# Sensoren.net
KiCad netlist of a schematic drawn in Altium Designer
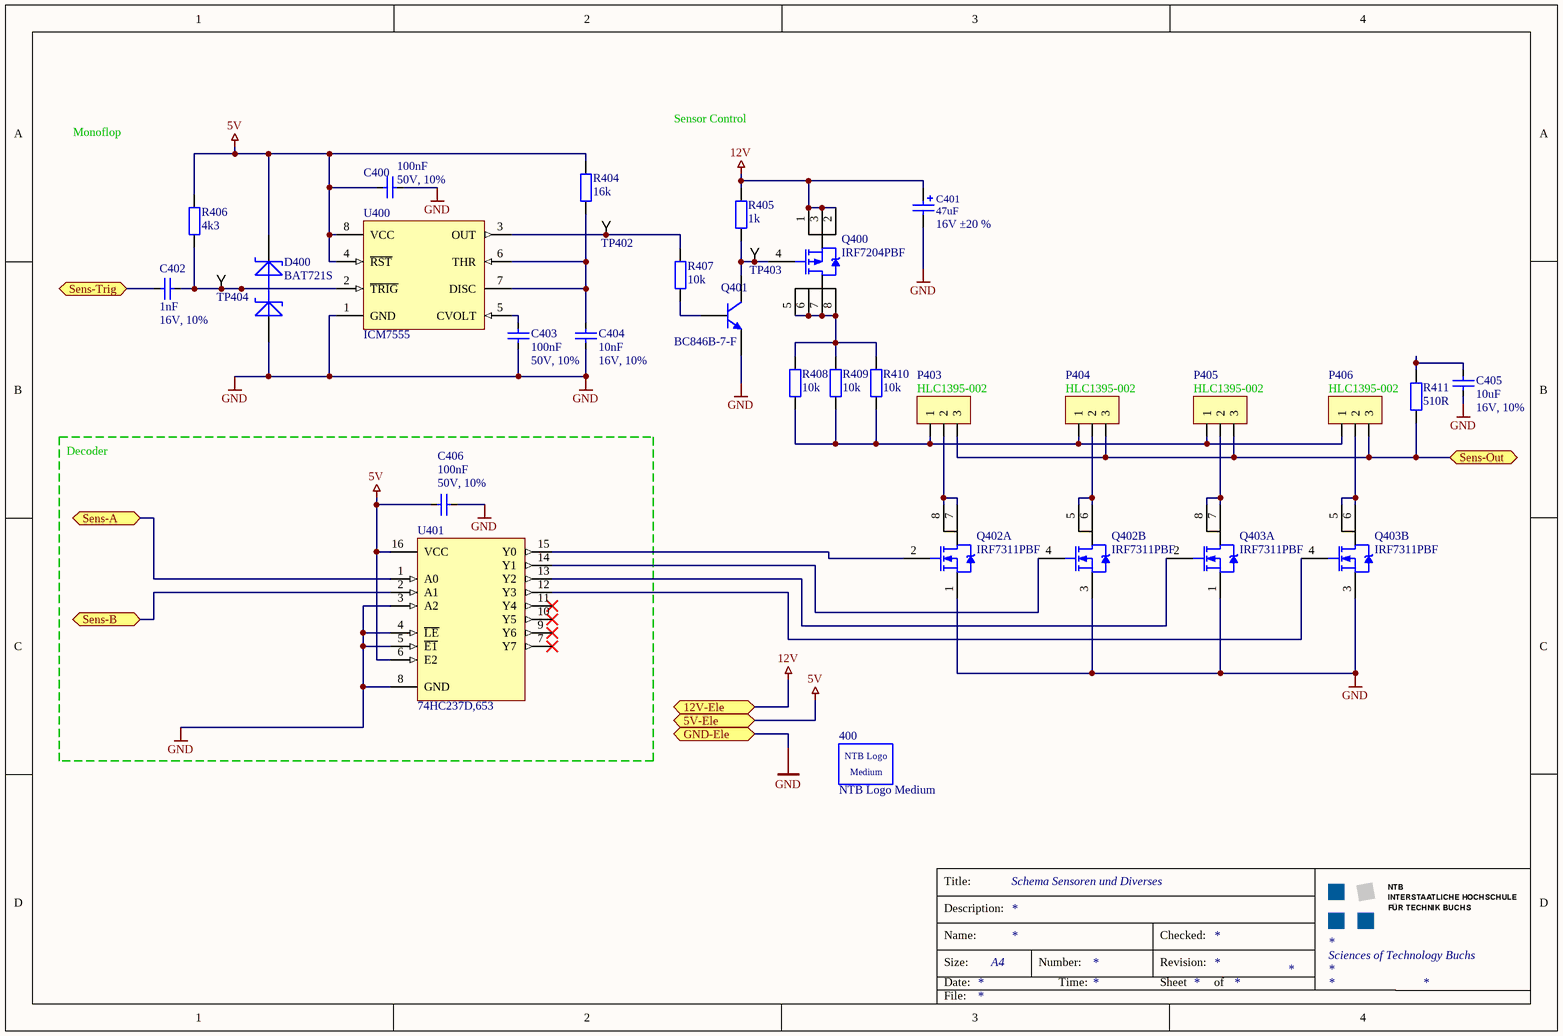
[diagram p0: Sensoren.SchDoc]

(export (version "E")
  (design (tool "Eeschema 10.0.6"))
  (components
    (comp (ref "400")
      (value "NTB Logo Medium")
      (footprint "NTB Logo Medium")
      (libsource (lib "IR-Sensor") (part "NTB Logo Medium"))
    )
    (comp (ref "C400")
      (value "100nF")
      (footprint "CAP-0805[2012]")
      (description "100n 50V X7R MLCC 0805 (1608 Metric)")
      (fields (field (name "TOLERANCE") "10%") (field (name "VALADDON") "50V, 10%"))
      (libsource (lib "IR-Sensor") (part "MLCC 0805 100n 50V"))
    )
    (comp (ref "C401")
      (value "47uF")
      (footprint "CDE_CAP AVE CODE D_H")
      (description "ELKO, 47uF, 16V, CDE_AVE476M16D16T-F_AVE CODE D")
      (fields
        (field (name "MANUFACTURER") "Cornell Dubilier")
        (field (name "VALUEADDON") "16V ±20 %")
        (field (name "Comment") "AVE476M16D16T-F")
        (field (name "PUBLISHER") "Stefan Ursella, M.Eng")
      )
      (libsource (lib "IR-Sensor") (part "ELKO 47uF 16V"))
    )
    (comp (ref "C402")
      (value "1nF")
      (footprint "CAP-0805[2012]")
      (description "MLCC - SMD/SMT 0805 1000pF 16V C0G 10%")
      (fields
        (field (name "MANUFACTURER") "Vishay")
        (field (name "VALUEADDON") "16V, 10%")
        (field (name "PUBLISHER") "SCLM")
      )
      (libsource (lib "IR-Sensor") (part "MLCC 0805 1n 16V"))
    )
    (comp (ref "C403")
      (value "100nF")
      (footprint "CAP-0805[2012]")
      (description "100n 50V X7R MLCC 0805 (1608 Metric)")
      (fields (field (name "TOLERANCE") "10%") (field (name "VALADDON") "50V, 10%"))
      (libsource (lib "IR-Sensor") (part "MLCC 0805 100n 50V"))
    )
    (comp (ref "C404")
      (value "10nF")
      (footprint "CAP-0805[2012]")
      (description "10n 16V X7R MLCC 0805")
      (fields
        (field (name "MANUFACTURER") "AVX")
        (field (name "VALUEADDON") "16V, 10%")
        (field (name "PUBLISHER") "SCLM")
      )
      (libsource (lib "IR-Sensor") (part "MLCC 0805 10n 16V"))
    )
    (comp (ref "C405")
      (value "10uF")
      (footprint "CAP-1206[3216]")
      (description "10u 16V X7R MLCC 1206 (3016 Metric)")
      (fields (field (name "TOLERANCE") "10%") (field (name "VALADDON") "16V, 10%"))
      (libsource (lib "IR-Sensor") (part "MLCC 1206 10u 16V"))
    )
    (comp (ref "C406")
      (value "100nF")
      (footprint "CAP-0805[2012]")
      (description "100n 50V X7R MLCC 0805 (1608 Metric)")
      (fields (field (name "TOLERANCE") "10%") (field (name "VALADDON") "50V, 10%"))
      (libsource (lib "IR-Sensor") (part "MLCC 0805 100n 50V"))
    )
    (comp (ref "D400")
      (value "BAT721S")
      (footprint "SOT-23")
      (description "NXP  BAT721S  SCHOTTKY-DIODE, 2FACH")
      (fields (field (name "MANUFACTURER") "NXP") (field (name "PUBLISHER") "SCNP"))
      (libsource (lib "IR-Sensor") (part "BAT721S-SOT23"))
    )
    (comp (ref "P403")
      (value "3 Pin Header Buchse")
      (footprint "3PIN HEADER SOCKET 2.54MM")
      (description "3 Pin Header 2.54mm Buchse")
      (libsource (lib "IR-Sensor") (part "3 Pin Header Buchse"))
    )
    (comp (ref "P404")
      (value "3 Pin Header Buchse")
      (footprint "3PIN HEADER SOCKET 2.54MM")
      (description "3 Pin Header 2.54mm Buchse")
      (libsource (lib "IR-Sensor") (part "3 Pin Header Buchse"))
    )
    (comp (ref "P405")
      (value "3 Pin Header Buchse")
      (footprint "3PIN HEADER SOCKET 2.54MM")
      (description "3 Pin Header 2.54mm Buchse")
      (libsource (lib "IR-Sensor") (part "3 Pin Header Buchse"))
    )
    (comp (ref "P406")
      (value "3 Pin Header Buchse")
      (footprint "3PIN HEADER SOCKET 2.54MM")
      (description "3 Pin Header 2.54mm Buchse")
      (libsource (lib "IR-Sensor") (part "3 Pin Header Buchse"))
    )
    (comp (ref "Q400")
      (value "IRF7204PBF")
      (footprint "SOIC-8")
      (description "High Power P-Kanal Mosfet")
      (fields
        (field (name "MANUFACTURER") "International Rectifiers")
        (field (name "PUBLISHER") "Altium Limited")
      )
      (libsource (lib "IR-Sensor") (part "IRF7204"))
    )
    (comp (ref "Q401")
      (value "BC846B-7-F")
      (footprint "SOT-23")
      (description "NPN General-purpose Transistor")
      (fields (field (name "MANUFACTURER") "DIODES INC") (field (name "PUBLISHER") "Altium Limited"))
      (libsource (lib "IR-Sensor") (part "BC846B-SOT23"))
    )
    (comp (ref "Q402")
      (value "IRF7311PBF")
      (footprint "SOIC-8")
      (description "Dual N-Kanal Mosfet")
      (fields
        (field (name "MANUFACTURER") "International Rectifier")
        (field (name "PUBLISHER") "Altium Limited")
      )
      (libsource (lib "IR-Sensor") (part "IRF7311"))
    )
    (comp (ref "Q403")
      (value "IRF7311PBF")
      (footprint "SOIC-8")
      (description "Dual N-Kanal Mosfet")
      (fields
        (field (name "MANUFACTURER") "International Rectifier")
        (field (name "PUBLISHER") "Altium Limited")
      )
      (libsource (lib "IR-Sensor") (part "IRF7311"))
    )
    (comp (ref "R404")
      (value "16k")
      (footprint "RES-0805[2012]")
      (description "0805 (2013 Metric) 1/10 W 10K 1 Thick Film Chip Resistor")
      (fields (field (name "POWER") "1/10 W") (field (name "TOLERANCE") "1%"))
      (libsource (lib "IR-Sensor") (part "RES 0805"))
    )
    (comp (ref "R405")
      (value "1k")
      (footprint "RES-0805[2012]")
      (description "0805 (2013 Metric) 1/10 W 10K 1 Thick Film Chip Resistor")
      (fields (field (name "POWER") "1/10 W") (field (name "TOLERANCE") "1%"))
      (libsource (lib "IR-Sensor") (part "RES 0805"))
    )
    (comp (ref "R406")
      (value "4k3")
      (footprint "RES-0805[2012]")
      (description "0805 (2013 Metric) 1/10 W 10K 1 Thick Film Chip Resistor")
      (fields (field (name "POWER") "1/10 W") (field (name "TOLERANCE") "1%"))
      (libsource (lib "IR-Sensor") (part "RES 0805"))
    )
    (comp (ref "R407")
      (value "10k")
      (footprint "RES-0805[2012]")
      (description "0805 (2013 Metric) 1/10 W 10K 1 Thick Film Chip Resistor")
      (fields (field (name "POWER") "1/10 W") (field (name "TOLERANCE") "1%"))
      (libsource (lib "IR-Sensor") (part "RES 0805"))
    )
    (comp (ref "R408")
      (value "10k")
      (footprint "RES-0805[2012]")
      (description "0805 (2013 Metric) 1/10 W 10K 1 Thick Film Chip Resistor")
      (fields (field (name "POWER") "1/10 W") (field (name "TOLERANCE") "1%"))
      (libsource (lib "IR-Sensor") (part "RES 0805"))
    )
    (comp (ref "R409")
      (value "10k")
      (footprint "RES-0805[2012]")
      (description "0805 (2013 Metric) 1/10 W 10K 1 Thick Film Chip Resistor")
      (fields (field (name "POWER") "1/10 W") (field (name "TOLERANCE") "1%"))
      (libsource (lib "IR-Sensor") (part "RES 0805"))
    )
    (comp (ref "R410")
      (value "10k")
      (footprint "RES-0805[2012]")
      (description "0805 (2013 Metric) 1/10 W 10K 1 Thick Film Chip Resistor")
      (fields (field (name "POWER") "1/10 W") (field (name "TOLERANCE") "1%"))
      (libsource (lib "IR-Sensor") (part "RES 0805"))
    )
    (comp (ref "R411")
      (value "510R")
      (footprint "RES-0805[2012]")
      (description "0805 (2013 Metric) 1/10 W 10K 1 Thick Film Chip Resistor")
      (fields (field (name "POWER") "1/10 W") (field (name "TOLERANCE") "1%"))
      (libsource (lib "IR-Sensor") (part "RES 0805"))
    )
    (comp (ref "TP402")
      (value "Testpoint SMD 1206")
      (footprint "TP-SMD-1206")
      (description "Testpoint xSmall")
      (libsource (lib "IR-Sensor") (part "Testpoint SMD 1206"))
    )
    (comp (ref "TP403")
      (value "Testpoint SMD 1206")
      (footprint "TP-SMD-1206")
      (description "Testpoint xSmall")
      (libsource (lib "altium-import") (part "root_0_Testpoint SMD 1206_"))
    )
    (comp (ref "TP404")
      (value "Testpoint SMD 1206")
      (footprint "TP-SMD-1206")
      (description "Testpoint xSmall")
      (libsource (lib "IR-Sensor") (part "Testpoint SMD 1206"))
    )
    (comp (ref "U400")
      (value "ICM7555")
      (footprint "SOIC-8")
      (description "General purpose CMOS timer")
      (fields
        (field (name "MANUFACTURER") "National Semiconductor")
        (field (name "PUBLISHER") "Altium Hobart Technology Centre")
      )
      (libsource (lib "IR-Sensor") (part "ICM7555-SOIC8"))
    )
    (comp (ref "U401")
      (value "74HC237D,653")
      (footprint "SOIC-16")
      (description "3-to-8 line decoder, demultiplexer, NXP, SO16")
      (fields (field (name "MANUFACTURER") "NXP") (field (name "PUBLISHER") "SCLM"))
      (libsource (lib "IR-Sensor") (part "74HC237D-SOIC16"))
    )
  )
  (nets
    (net (code "1") (name "/Sens-A") (class "Default")
      (node (ref "U401") (pin "1") (pinfunction "A0_1") (pintype "input"))
    )
    (net (code "2") (name "/Sens-B") (class "Default")
      (node (ref "U401") (pin "2") (pinfunction "A1_2") (pintype "input"))
    )
    (net (code "3") (name "/Sens-Out") (class "Default")
      (node (ref "P403") (pin "3") (pinfunction "3_3") (pintype "passive"))
      (node (ref "P404") (pin "3") (pinfunction "3_3") (pintype "passive"))
      (node (ref "P405") (pin "3") (pinfunction "3_3") (pintype "passive"))
      (node (ref "P406") (pin "3") (pinfunction "3_3") (pintype "passive"))
      (node (ref "R411") (pin "1") (pinfunction "1_1") (pintype "passive"))
    )
    (net (code "4") (name "/Sens-Trig") (class "Default")
      (node (ref "C402") (pin "1") (pinfunction "Pos_1") (pintype "passive"))
    )
    (net (code "5") (name "5V") (class "Default")
      (node (ref "C400") (pin "1") (pinfunction "Pos_1") (pintype "passive"))
      (node (ref "C406") (pin "1") (pinfunction "Pos_1") (pintype "passive"))
      (node (ref "D400") (pin "2") (pinfunction "cathode2_2") (pintype "passive"))
      (node (ref "R404") (pin "2") (pinfunction "2_2") (pintype "passive"))
      (node (ref "R406") (pin "2") (pinfunction "2_2") (pintype "passive"))
      (node (ref "U400") (pin "4") (pinfunction "~{RST}_4") (pintype "input"))
      (node (ref "U400") (pin "8") (pinfunction "VCC_8") (pintype "power_in"))
      (node (ref "U401") (pin "16") (pinfunction "VCC_16") (pintype "power_in"))
      (node (ref "U401") (pin "6") (pinfunction "E2_6") (pintype "input"))
    )
    (net (code "6") (name "12V") (class "Default")
      (node (ref "C401") (pin "1") (pinfunction "Pos_1") (pintype "passive"))
      (node (ref "Q400") (pin "1") (pinfunction "S_1") (pintype "passive"))
      (node (ref "Q400") (pin "2") (pinfunction "S_2") (pintype "passive"))
      (node (ref "Q400") (pin "3") (pinfunction "S_3") (pintype "passive"))
      (node (ref "R405") (pin "2") (pinfunction "2_2") (pintype "passive"))
    )
    (net (code "7") (name "GND") (class "Default")
      (node (ref "C400") (pin "2") (pinfunction "Neg_2") (pintype "passive"))
      (node (ref "C401") (pin "2") (pinfunction "Neg_2") (pintype "passive"))
      (node (ref "C403") (pin "2") (pinfunction "Neg_2") (pintype "passive"))
      (node (ref "C404") (pin "2") (pinfunction "Neg_2") (pintype "passive"))
      (node (ref "C405") (pin "2") (pinfunction "Neg_2") (pintype "passive"))
      (node (ref "C406") (pin "2") (pinfunction "Neg_2") (pintype "passive"))
      (node (ref "D400") (pin "1") (pinfunction "Anode1_1") (pintype "passive"))
      (node (ref "Q401") (pin "2") (pinfunction "E_2") (pintype "passive"))
      (node (ref "Q402") (pin "1") (pinfunction "S_1") (pintype "passive"))
      (node (ref "Q402") (pin "3") (pinfunction "S_3") (pintype "passive"))
      (node (ref "Q403") (pin "1") (pinfunction "S_1") (pintype "passive"))
      (node (ref "Q403") (pin "3") (pinfunction "S_3") (pintype "passive"))
      (node (ref "U400") (pin "1") (pinfunction "GND_1") (pintype "power_in"))
      (node (ref "U401") (pin "3") (pinfunction "A2_3") (pintype "input"))
      (node (ref "U401") (pin "4") (pinfunction "LE_4") (pintype "input"))
      (node (ref "U401") (pin "5") (pinfunction "E1_5") (pintype "input"))
      (node (ref "U401") (pin "8") (pinfunction "GND_8") (pintype "power_in"))
    )
    (net (code "8") (name "Net-(C402-Neg)") (class "Default")
      (node (ref "C402") (pin "2") (pinfunction "Neg_2") (pintype "passive"))
      (node (ref "D400") (pin "3") (pinfunction "Cathode1,_anode2_3") (pintype "passive"))
      (node (ref "R406") (pin "1") (pinfunction "1_1") (pintype "passive"))
      (node (ref "TP404") (pin "1") (pinfunction "0_1") (pintype "passive"))
      (node (ref "U400") (pin "2") (pinfunction "TRIG_2") (pintype "input"))
    )
    (net (code "9") (name "Net-(C403-Pos)") (class "Default")
      (node (ref "C403") (pin "1") (pinfunction "Pos_1") (pintype "passive"))
      (node (ref "U400") (pin "5") (pinfunction "CVOLT_5") (pintype "input"))
    )
    (net (code "10") (name "Net-(C404-Pos)") (class "Default")
      (node (ref "C404") (pin "1") (pinfunction "Pos_1") (pintype "passive"))
      (node (ref "R404") (pin "1") (pinfunction "1_1") (pintype "passive"))
      (node (ref "U400") (pin "6") (pinfunction "THR_6") (pintype "input"))
      (node (ref "U400") (pin "7") (pinfunction "DISC_7") (pintype "open_collector"))
    )
    (net (code "11") (name "Net-(C405-Pos)") (class "Default")
      (node (ref "C405") (pin "1") (pinfunction "Pos_1") (pintype "passive"))
      (node (ref "R411") (pin "2") (pinfunction "2_2") (pintype "passive"))
    )
    (net (code "12") (name "Net-(P403-Pad1)") (class "Default")
      (node (ref "P403") (pin "1") (pinfunction "1_1") (pintype "passive"))
      (node (ref "P404") (pin "1") (pinfunction "1_1") (pintype "passive"))
      (node (ref "P405") (pin "1") (pinfunction "1_1") (pintype "passive"))
      (node (ref "P406") (pin "1") (pinfunction "1_1") (pintype "passive"))
      (node (ref "R408") (pin "1") (pinfunction "1_1") (pintype "passive"))
      (node (ref "R409") (pin "1") (pinfunction "1_1") (pintype "passive"))
      (node (ref "R410") (pin "1") (pinfunction "1_1") (pintype "passive"))
    )
    (net (code "13") (name "Net-(P403-Pad2)") (class "Default")
      (node (ref "P403") (pin "2") (pinfunction "2_2") (pintype "passive"))
      (node (ref "Q402") (pin "7") (pinfunction "D_7") (pintype "passive"))
      (node (ref "Q402") (pin "8") (pinfunction "D_8") (pintype "passive"))
    )
    (net (code "14") (name "Net-(P404-Pad2)") (class "Default")
      (node (ref "P404") (pin "2") (pinfunction "2_2") (pintype "passive"))
      (node (ref "Q402") (pin "5") (pinfunction "D_5") (pintype "passive"))
      (node (ref "Q402") (pin "6") (pinfunction "D_6") (pintype "passive"))
    )
    (net (code "15") (name "Net-(P405-Pad2)") (class "Default")
      (node (ref "P405") (pin "2") (pinfunction "2_2") (pintype "passive"))
      (node (ref "Q403") (pin "7") (pinfunction "D_7") (pintype "passive"))
      (node (ref "Q403") (pin "8") (pinfunction "D_8") (pintype "passive"))
    )
    (net (code "16") (name "Net-(P406-Pad2)") (class "Default")
      (node (ref "P406") (pin "2") (pinfunction "2_2") (pintype "passive"))
      (node (ref "Q403") (pin "5") (pinfunction "D_5") (pintype "passive"))
      (node (ref "Q403") (pin "6") (pinfunction "D_6") (pintype "passive"))
    )
    (net (code "17") (name "Net-(Q400-D-Pad5)") (class "Default")
      (node (ref "Q400") (pin "5") (pinfunction "D_5") (pintype "passive"))
      (node (ref "Q400") (pin "6") (pinfunction "D_6") (pintype "passive"))
      (node (ref "Q400") (pin "7") (pinfunction "D_7") (pintype "passive"))
      (node (ref "Q400") (pin "8") (pinfunction "D_8") (pintype "passive"))
      (node (ref "R408") (pin "2") (pinfunction "2_2") (pintype "passive"))
      (node (ref "R409") (pin "2") (pinfunction "2_2") (pintype "passive"))
      (node (ref "R410") (pin "2") (pinfunction "2_2") (pintype "passive"))
    )
    (net (code "18") (name "Net-(Q400-G)") (class "Default")
      (node (ref "Q400") (pin "4") (pinfunction "G_4") (pintype "passive"))
      (node (ref "Q401") (pin "3") (pinfunction "C_3") (pintype "passive"))
      (node (ref "R405") (pin "1") (pinfunction "1_1") (pintype "passive"))
      (node (ref "TP403") (pin "1") (pinfunction "0_1") (pintype "passive"))
    )
    (net (code "19") (name "Net-(Q401-B)") (class "Default")
      (node (ref "Q401") (pin "1") (pinfunction "B_1") (pintype "passive"))
      (node (ref "R407") (pin "2") (pinfunction "2_2") (pintype "passive"))
    )
    (net (code "20") (name "Net-(Q402A-G)") (class "Default")
      (node (ref "Q402") (pin "2") (pinfunction "G_2") (pintype "passive"))
      (node (ref "U401") (pin "15") (pinfunction "Y0_15") (pintype "output"))
    )
    (net (code "21") (name "Net-(Q402B-G)") (class "Default")
      (node (ref "Q402") (pin "4") (pinfunction "G_4") (pintype "passive"))
      (node (ref "U401") (pin "14") (pinfunction "Y1_14") (pintype "output"))
    )
    (net (code "22") (name "Net-(Q403A-G)") (class "Default")
      (node (ref "Q403") (pin "2") (pinfunction "G_2") (pintype "passive"))
      (node (ref "U401") (pin "13") (pinfunction "Y2_13") (pintype "output"))
    )
    (net (code "23") (name "Net-(Q403B-G)") (class "Default")
      (node (ref "Q403") (pin "4") (pinfunction "G_4") (pintype "passive"))
      (node (ref "U401") (pin "12") (pinfunction "Y3_12") (pintype "output"))
    )
    (net (code "24") (name "Net-(TP402-0)") (class "Default")
      (node (ref "R407") (pin "1") (pinfunction "1_1") (pintype "passive"))
      (node (ref "TP402") (pin "1") (pinfunction "0_1") (pintype "passive"))
      (node (ref "U400") (pin "3") (pinfunction "OUT_3") (pintype "output"))
    )
    (net (code "25") (name "unconnected-(U401-Y4-Pad11)") (class "Default")
      (node (ref "U401") (pin "11") (pinfunction "Y4_11") (pintype "output+no_connect"))
    )
    (net (code "26") (name "unconnected-(U401-Y5-Pad10)") (class "Default")
      (node (ref "U401") (pin "10") (pinfunction "Y5_10") (pintype "output+no_connect"))
    )
    (net (code "27") (name "unconnected-(U401-Y6-Pad9)") (class "Default")
      (node (ref "U401") (pin "9") (pinfunction "Y6_9") (pintype "output+no_connect"))
    )
    (net (code "28") (name "unconnected-(U401-Y7-Pad7)") (class "Default")
      (node (ref "U401") (pin "7") (pinfunction "Y7_7") (pintype "output+no_connect"))
    )
  )
)
